# 03-INPUT.net
KiCad netlist of a schematic drawn in Altium Designer
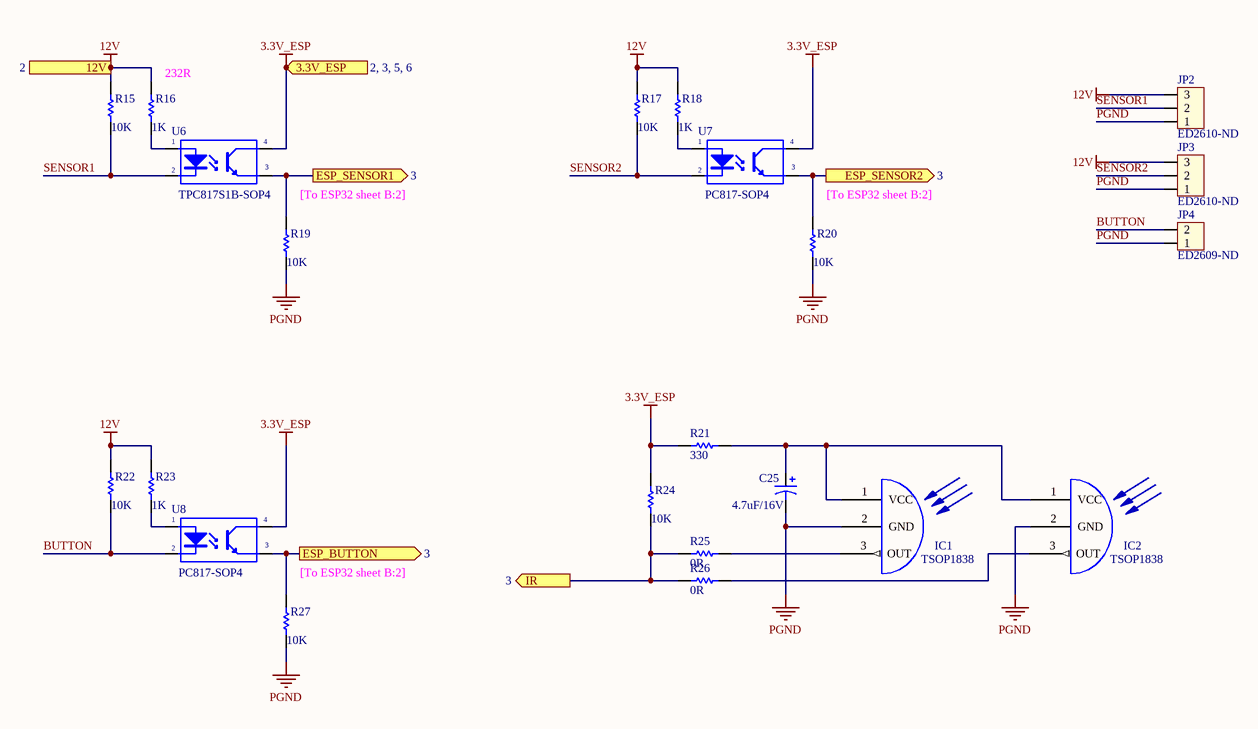
[diagram p0: 03-INPUT.SchDoc]

(export (version "E")
  (design (tool "Eeschema 10.0.6"))
  (components
    (comp (ref "C25")
      (value "4.7uF/16V")
      (footprint "C0805")
      (description "Polarized Capacitor (Radial)")
      (fields (field (name "Comment") "Cap Pol1") (field (name "PUBLISHER") "Altium Limited"))
      (libsource (lib "Miscellaneous Devices") (part "Cap Pol1"))
    )
    (comp (ref "IC1")
      (value "TSOP1838")
      (footprint "TSOP1838")
      (libsource (lib "Tran Tuan") (part "TSOP1838"))
    )
    (comp (ref "IC2")
      (value "TSOP1838")
      (footprint "TSOP1838")
      (libsource (lib "Tran Tuan") (part "TSOP1838"))
    )
    (comp (ref "JP2")
      (value "ED2610-ND")
      (footprint "DOMINO_OSTTC_3P")
      (description "3 Position Wire to Board Terminal Block Horizontal with Board 0.200\" (5.08mm) Through Hole")
      (libsource (lib "lpson") (part "Con3"))
    )
    (comp (ref "JP3")
      (value "ED2610-ND")
      (footprint "DOMINO_OSTTC_3P")
      (description "3 Position Wire to Board Terminal Block Horizontal with Board 0.200\" (5.08mm) Through Hole")
      (libsource (lib "lpson") (part "Con3"))
    )
    (comp (ref "JP4")
      (value "ED2609-ND")
      (footprint "DOMINO_OSTTC_2P")
      (description "2 Position Wire to Board Terminal Block Horizontal with Board 0.200\" (5.08mm) Through Hole")
      (libsource (lib "lpson") (part "Con2"))
    )
    (comp (ref "R15")
      (value "10K")
      (footprint "Res 0805 SMD")
      (description "RES SMD 10K OHM 1% 1/10W 0603")
      (fields
        (field (name "MANUFACTURER") "Yageo")
        (field (name "MANUFACTURER PART NUMBER") "RC0603FR-0710KL")
      )
      (libsource (lib "GSHT_181013") (part "10K/R0603/1%"))
    )
    (comp (ref "R16")
      (value "1K")
      (footprint "Res 0805 SMD")
      (description "1 kOhms ±1% 0.125W, 1/8W Chip Resistor 0805 (2012 Metric) Automotive AEC-Q200 Thick Film")
      (libsource (lib "GSHT_181013") (part "10K/R0603/1%"))
    )
    (comp (ref "R17")
      (value "10K")
      (footprint "Res 0805 SMD")
      (description "RES SMD 10K OHM 1% 1/10W 0603")
      (fields
        (field (name "MANUFACTURER") "Yageo")
        (field (name "MANUFACTURER PART NUMBER") "RC0603FR-0710KL")
      )
      (libsource (lib "GSHT_181013") (part "10K/R0603/1%"))
    )
    (comp (ref "R18")
      (value "1K")
      (footprint "Res 0805 SMD")
      (description "1 kOhms ±1% 0.125W, 1/8W Chip Resistor 0805 (2012 Metric) Automotive AEC-Q200 Thick Film")
      (libsource (lib "GSHT_181013") (part "10K/R0603/1%"))
    )
    (comp (ref "R19")
      (value "10K")
      (footprint "Res 0805 SMD")
      (description "RES SMD 249K OHM 1% 1/10W 0805")
      (fields
        (field (name "MANUFACTURER") "Yageo")
        (field (name "MANUFACTURER PART NUMBER") "RC0603FR-07249KL")
      )
      (libsource (lib "GSHT_181013") (part "249K/R0805/1%"))
    )
    (comp (ref "R20")
      (value "10K")
      (footprint "Res 0805 SMD")
      (description "RES SMD 249K OHM 1% 1/10W 0805")
      (fields
        (field (name "MANUFACTURER") "Yageo")
        (field (name "MANUFACTURER PART NUMBER") "RC0603FR-07249KL")
      )
      (libsource (lib "GSHT_181013") (part "249K/R0805/1%"))
    )
    (comp (ref "R21")
      (value "330")
      (footprint "Res 0805 SMD")
      (description "RES SMD 249K OHM 1% 1/10W 0805")
      (fields
        (field (name "MANUFACTURER") "Yageo")
        (field (name "MANUFACTURER PART NUMBER") "RC0603FR-07249KL")
      )
      (libsource (lib "GSHT_181013") (part "249K/R0805/1%"))
    )
    (comp (ref "R22")
      (value "10K")
      (footprint "Res 0805 SMD")
      (description "RES SMD 10K OHM 1% 1/10W 0603")
      (fields
        (field (name "MANUFACTURER") "Yageo")
        (field (name "MANUFACTURER PART NUMBER") "RC0603FR-0710KL")
      )
      (libsource (lib "GSHT_181013") (part "10K/R0603/1%"))
    )
    (comp (ref "R23")
      (value "1K")
      (footprint "Res 0805 SMD")
      (description "1 kOhms ±1% 0.125W, 1/8W Chip Resistor 0805 (2012 Metric) Automotive AEC-Q200 Thick Film")
      (libsource (lib "GSHT_181013") (part "10K/R0603/1%"))
    )
    (comp (ref "R24")
      (value "10K")
      (footprint "Res 0805 SMD")
      (description "RES SMD 249K OHM 1% 1/10W 0805")
      (fields
        (field (name "MANUFACTURER") "Yageo")
        (field (name "MANUFACTURER PART NUMBER") "RC0603FR-07249KL")
      )
      (libsource (lib "GSHT_181013") (part "249K/R0805/1%"))
    )
    (comp (ref "R25")
      (value "0R")
      (footprint "Res 0805 SMD")
      (description "RES SMD 249K OHM 1% 1/10W 0805")
      (fields
        (field (name "MANUFACTURER") "Yageo")
        (field (name "MANUFACTURER PART NUMBER") "RC0603FR-07249KL")
      )
      (libsource (lib "GSHT_181013") (part "249K/R0805/1%"))
    )
    (comp (ref "R26")
      (value "0R")
      (footprint "Res 0805 SMD")
      (description "RES SMD 249K OHM 1% 1/10W 0805")
      (fields
        (field (name "MANUFACTURER") "Yageo")
        (field (name "MANUFACTURER PART NUMBER") "RC0603FR-07249KL")
      )
      (libsource (lib "GSHT_181013") (part "249K/R0805/1%"))
    )
    (comp (ref "R27")
      (value "10K")
      (footprint "Res 0805 SMD")
      (description "RES SMD 249K OHM 1% 1/10W 0805")
      (fields
        (field (name "MANUFACTURER") "Yageo")
        (field (name "MANUFACTURER PART NUMBER") "RC0603FR-07249KL")
      )
      (libsource (lib "GSHT_181013") (part "249K/R0805/1%"))
    )
    (comp (ref "U6")
      (value "TPC817S1B-SOP4")
      (footprint "TPC817-4SOP")
      (description "Optoisolator Transistor Output 5000Vrms 1 Channel 4-SOP")
      (libsource (lib "lpson") (part "PC817"))
    )
    (comp (ref "U7")
      (value "PC817-SOP4")
      (footprint "TPC817-4SOP")
      (description "Optoisolator Transistor Output 5000Vrms 1 Channel 4-SOP")
      (libsource (lib "lpson") (part "PC817"))
    )
    (comp (ref "U8")
      (value "PC817-SOP4")
      (footprint "TPC817-4SOP")
      (description "Optoisolator Transistor Output 5000Vrms 1 Channel 4-SOP")
      (libsource (lib "lpson") (part "PC817"))
    )
  )
  (nets
    (net (code "1") (name "/BUTTON") (class "Default")
      (node (ref "JP4") (pin "2") (pinfunction "2_2") (pintype "passive"))
      (node (ref "R22") (pin "1") (pinfunction "1_1") (pintype "passive"))
      (node (ref "U8") (pin "2") (pinfunction "K_2") (pintype "passive"))
    )
    (net (code "2") (name "/ESP_BUTTON") (class "Default")
      (node (ref "R27") (pin "2") (pinfunction "2_2") (pintype "passive"))
      (node (ref "U8") (pin "3") (pinfunction "E_3") (pintype "passive"))
    )
    (net (code "3") (name "/ESP_SENSOR1") (class "Default")
      (node (ref "R19") (pin "2") (pinfunction "2_2") (pintype "passive"))
      (node (ref "U6") (pin "3") (pinfunction "E_3") (pintype "passive"))
    )
    (net (code "4") (name "/ESP_SENSOR2") (class "Default")
      (node (ref "R20") (pin "2") (pinfunction "2_2") (pintype "passive"))
      (node (ref "U7") (pin "3") (pinfunction "E_3") (pintype "passive"))
    )
    (net (code "5") (name "/IR") (class "Default")
      (node (ref "R24") (pin "1") (pinfunction "1_1") (pintype "passive"))
      (node (ref "R25") (pin "2") (pinfunction "2_2") (pintype "passive"))
      (node (ref "R26") (pin "2") (pinfunction "2_2") (pintype "passive"))
    )
    (net (code "6") (name "/SENSOR1") (class "Default")
      (node (ref "JP2") (pin "2") (pinfunction "2_2") (pintype "passive"))
      (node (ref "R15") (pin "1") (pinfunction "1_1") (pintype "passive"))
      (node (ref "U6") (pin "2") (pinfunction "K_2") (pintype "passive"))
    )
    (net (code "7") (name "/SENSOR2") (class "Default")
      (node (ref "JP3") (pin "2") (pinfunction "2_2") (pintype "passive"))
      (node (ref "R17") (pin "1") (pinfunction "1_1") (pintype "passive"))
      (node (ref "U7") (pin "2") (pinfunction "K_2") (pintype "passive"))
    )
    (net (code "8") (name "3.3V_ESP") (class "Default")
      (node (ref "R21") (pin "2") (pinfunction "2_2") (pintype "passive"))
      (node (ref "R24") (pin "2") (pinfunction "2_2") (pintype "passive"))
      (node (ref "U6") (pin "4") (pinfunction "C_4") (pintype "passive"))
      (node (ref "U7") (pin "4") (pinfunction "C_4") (pintype "passive"))
      (node (ref "U8") (pin "4") (pinfunction "C_4") (pintype "passive"))
    )
    (net (code "9") (name "12V") (class "Default")
      (node (ref "JP2") (pin "3") (pinfunction "3_3") (pintype "passive"))
      (node (ref "JP3") (pin "3") (pinfunction "3_3") (pintype "passive"))
      (node (ref "R15") (pin "2") (pinfunction "2_2") (pintype "passive"))
      (node (ref "R16") (pin "2") (pinfunction "2_2") (pintype "passive"))
      (node (ref "R17") (pin "2") (pinfunction "2_2") (pintype "passive"))
      (node (ref "R18") (pin "2") (pinfunction "2_2") (pintype "passive"))
      (node (ref "R22") (pin "2") (pinfunction "2_2") (pintype "passive"))
      (node (ref "R23") (pin "2") (pinfunction "2_2") (pintype "passive"))
    )
    (net (code "10") (name "Net-(IC1-OUT)") (class "Default")
      (node (ref "IC1") (pin "3") (pinfunction "OUT_3") (pintype "output"))
      (node (ref "R25") (pin "1") (pinfunction "1_1") (pintype "passive"))
    )
    (net (code "11") (name "Net-(IC1-VCC)") (class "Default")
      (node (ref "C25") (pin "1") (pinfunction "1_1") (pintype "passive"))
      (node (ref "IC1") (pin "1") (pinfunction "VCC_1") (pintype "power_in"))
      (node (ref "IC2") (pin "1") (pinfunction "VCC_1") (pintype "power_in"))
      (node (ref "R21") (pin "1") (pinfunction "1_1") (pintype "passive"))
    )
    (net (code "12") (name "Net-(IC2-OUT)") (class "Default")
      (node (ref "IC2") (pin "3") (pinfunction "OUT_3") (pintype "output"))
      (node (ref "R26") (pin "1") (pinfunction "1_1") (pintype "passive"))
    )
    (net (code "13") (name "Net-(U6-A)") (class "Default")
      (node (ref "R16") (pin "1") (pinfunction "1_1") (pintype "passive"))
      (node (ref "U6") (pin "1") (pinfunction "A_1") (pintype "passive"))
    )
    (net (code "14") (name "Net-(U7-A)") (class "Default")
      (node (ref "R18") (pin "1") (pinfunction "1_1") (pintype "passive"))
      (node (ref "U7") (pin "1") (pinfunction "A_1") (pintype "passive"))
    )
    (net (code "15") (name "Net-(U8-A)") (class "Default")
      (node (ref "R23") (pin "1") (pinfunction "1_1") (pintype "passive"))
      (node (ref "U8") (pin "1") (pinfunction "A_1") (pintype "passive"))
    )
    (net (code "16") (name "PGND") (class "Default")
      (node (ref "C25") (pin "2") (pinfunction "2_2") (pintype "passive"))
      (node (ref "IC1") (pin "2") (pinfunction "GND_2") (pintype "power_in"))
      (node (ref "IC2") (pin "2") (pinfunction "GND_2") (pintype "power_in"))
      (node (ref "JP2") (pin "1") (pinfunction "1_1") (pintype "passive"))
      (node (ref "JP3") (pin "1") (pinfunction "1_1") (pintype "passive"))
      (node (ref "JP4") (pin "1") (pinfunction "1_1") (pintype "passive"))
      (node (ref "R19") (pin "1") (pinfunction "1_1") (pintype "passive"))
      (node (ref "R20") (pin "1") (pinfunction "1_1") (pintype "passive"))
      (node (ref "R27") (pin "1") (pinfunction "1_1") (pintype "passive"))
    )
  )
)
